# Main.net
KiCad netlist of a schematic drawn in Altium Designer
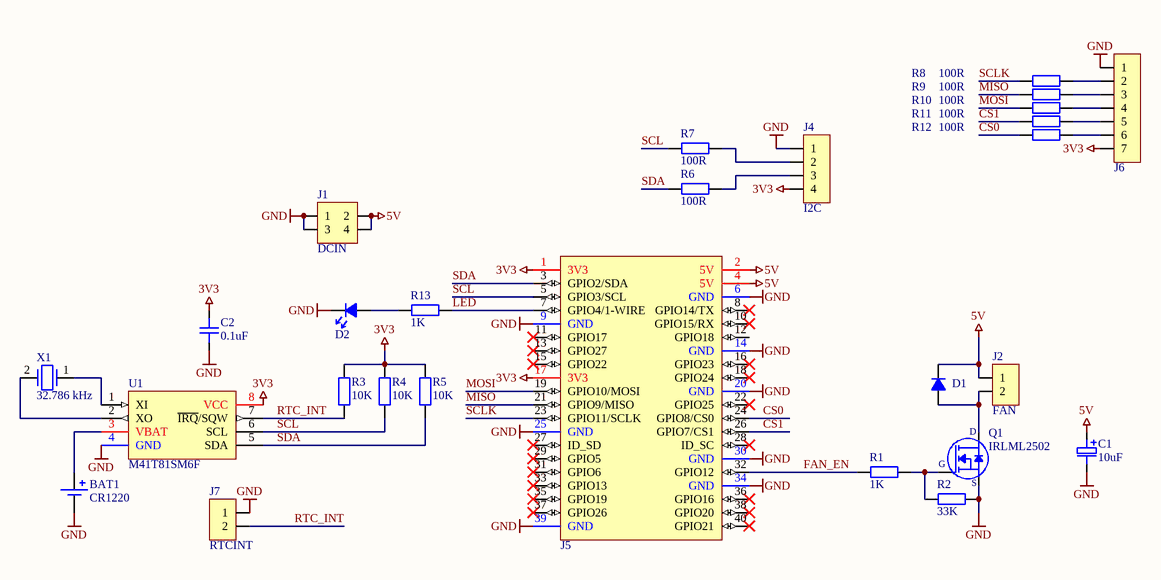
[diagram p0: Main.SchDoc]

(export (version "E")
  (design (tool "Eeschema 10.0.6"))
  (components
    (comp (ref "BAT1")
      (value "CR1220")
      (footprint "BC501SM")
      (description "Single Cell Battery")
      (libsource (lib "AG.Holder") (part "BC501SM"))
    )
    (comp (ref "C1")
      (value "10uF")
      (footprint "C_EL_B_4MM_RF_M")
      (description "Polarized Capacitor")
      (fields (field (name "TOLERANCE") "?") (field (name "MANUFACTURER") "Generic Brand"))
      (libsource (lib "AG.Generic") (part "C-P"))
    )
    (comp (ref "C2")
      (value "0.1uF")
      (footprint "0603C_RF_M")
      (description "Capacitor")
      (fields (field (name "TOLERANCE") "20%") (field (name "MANUFACTURER") "Generic Brand"))
      (libsource (lib "AG.Generic") (part "C"))
    )
    (comp (ref "D1")
      (value "D")
      (footprint "ONSEMI_DO214AC_RF_M")
      (description "Diode (Rectifier)")
      (fields (field (name "MANUFACTURER") "Generic Brand"))
      (libsource (lib "AG.Generic") (part "D"))
    )
    (comp (ref "D2")
      (value "Unspecified")
      (footprint "0805LED_RF_M")
      (description "LED")
      (fields (field (name "MANUFACTURER") "Generic Brand"))
      (libsource (lib "AG.Generic") (part "LED"))
    )
    (comp (ref "J1")
      (value "DCIN")
      (footprint "HEADER-2.54-4P-2R")
      (description "Rectangular Header Male Pins Double Row 4 Positions")
      (libsource (lib "AG.Connectors") (part "PINHDR-4P-2R"))
    )
    (comp (ref "J2")
      (value "FAN")
      (footprint "HEADER-2.54-2P1")
      (description "Pin Header Single Row 2 Positions")
      (libsource (lib "AG.Connectors") (part "PINHDR-2P1"))
    )
    (comp (ref "J4")
      (value "I2C")
      (footprint "AG.Connectors:HEADER-2.54-4P1")
      (description "Generic Pin Header 4x1")
      (libsource (lib "AG.Connectors") (part "PINHDR-4P1"))
    )
    (comp (ref "J5")
      (value "RPI4-40P")
      (footprint "HEADER-2.54-RCPT-40P-2R-BTL")
      (description "Raspberry Pi 4 Model B+ Compatible GPIO Header")
      (libsource (lib "AG.Connectors") (part "RPI4-40P"))
    )
    (comp (ref "J6")
      (value "PINHDR-7P1")
      (footprint "HEADER-2.54-7P1")
      (description "Pin Header Single Row 7 Positions")
      (libsource (lib "AG.Connectors") (part "PINHDR-7P1"))
    )
    (comp (ref "J7")
      (value "RTCINT")
      (footprint "HEADER-2.54-2P1")
      (description "Pin Header Single Row 2 Positions")
      (libsource (lib "") (part "PINHDR-2P1_1"))
    )
    (comp (ref "Q1")
      (value "IRLML2502")
      (footprint "IRLML_SOT-23")
      (description "MOSFET N-CH 20V 4.2A SOT23")
      (fields (field (name "MANUFACTURER") "Infineon") (field (name "MANUFACTURER PART NO") "IRLML2502TRPBF"))
      (libsource (lib "AG.Discrete") (part "IRLML2502"))
    )
    (comp (ref "R1")
      (value "1K")
      (footprint "0603R_RF_M")
      (description "Resistor")
      (fields (field (name "TOLERANCE") "?") (field (name "MANUFACTURER") "Generic Brand"))
      (libsource (lib "AG.Generic") (part "R"))
    )
    (comp (ref "R2")
      (value "33K")
      (footprint "0603R_RF_M")
      (description "Resistor")
      (fields (field (name "TOLERANCE") "?") (field (name "MANUFACTURER") "Generic Brand"))
      (libsource (lib "AG.Generic") (part "R"))
    )
    (comp (ref "R3")
      (value "10K")
      (footprint "0603R_RF_M")
      (description "Resistor")
      (fields (field (name "TOLERANCE") "?") (field (name "MANUFACTURER") "Generic Brand"))
      (libsource (lib "AG.Generic") (part "R"))
    )
    (comp (ref "R4")
      (value "10K")
      (footprint "0603R_RF_M")
      (description "Resistor")
      (fields (field (name "TOLERANCE") "?") (field (name "MANUFACTURER") "Generic Brand"))
      (libsource (lib "AG.Generic") (part "R"))
    )
    (comp (ref "R5")
      (value "10K")
      (footprint "0603R_RF_M")
      (description "Resistor")
      (fields (field (name "TOLERANCE") "?") (field (name "MANUFACTURER") "Generic Brand"))
      (libsource (lib "AG.Generic") (part "R"))
    )
    (comp (ref "R6")
      (value "100R")
      (footprint "0603R_RF_M")
      (description "Resistor")
      (fields (field (name "TOLERANCE") "?") (field (name "MANUFACTURER") "Generic Brand"))
      (libsource (lib "AG.Generic") (part "R"))
    )
    (comp (ref "R7")
      (value "100R")
      (footprint "0603R_RF_M")
      (description "Resistor")
      (fields (field (name "TOLERANCE") "?") (field (name "MANUFACTURER") "Generic Brand"))
      (libsource (lib "AG.Generic") (part "R"))
    )
    (comp (ref "R8")
      (value "100R")
      (footprint "0603R_RF_M")
      (description "Resistor")
      (fields (field (name "TOLERANCE") "?") (field (name "MANUFACTURER") "Generic Brand"))
      (libsource (lib "AG.Generic") (part "R"))
    )
    (comp (ref "R9")
      (value "100R")
      (footprint "0603R_RF_M")
      (description "Resistor")
      (fields (field (name "TOLERANCE") "?") (field (name "MANUFACTURER") "Generic Brand"))
      (libsource (lib "AG.Generic") (part "R"))
    )
    (comp (ref "R10")
      (value "100R")
      (footprint "0603R_RF_M")
      (description "Resistor")
      (fields (field (name "TOLERANCE") "?") (field (name "MANUFACTURER") "Generic Brand"))
      (libsource (lib "AG.Generic") (part "R"))
    )
    (comp (ref "R11")
      (value "100R")
      (footprint "0603R_RF_M")
      (description "Resistor")
      (fields (field (name "TOLERANCE") "?") (field (name "MANUFACTURER") "Generic Brand"))
      (libsource (lib "AG.Generic") (part "R"))
    )
    (comp (ref "R12")
      (value "100R")
      (footprint "0603R_RF_M")
      (description "Resistor")
      (fields (field (name "TOLERANCE") "?") (field (name "MANUFACTURER") "Generic Brand"))
      (libsource (lib "AG.Generic") (part "R"))
    )
    (comp (ref "R13")
      (value "1K")
      (footprint "0603R_RF_M")
      (description "Resistor")
      (fields (field (name "TOLERANCE") "?") (field (name "MANUFACTURER") "Generic Brand"))
      (libsource (lib "AG.Generic") (part "R"))
    )
    (comp (ref "U1")
      (value "M41T81SM6F")
      (footprint "ST_SOIC-8")
      (description "IC RTC CLK/CALENDAR I2C 8-SOIC")
      (fields
        (field (name "MANUFACTURER") "STMicroelectronics")
        (field (name "ALTERNATIVE SUPPLIER PART NO") "9000354105")
      )
      (libsource (lib "AG.IC") (part "M41T81SM6F"))
    )
    (comp (ref "X1")
      (value "32.786 kHz")
      (footprint "XTAL_3215")
      (description "Crystal Resonator (2 Leads)")
      (fields (field (name "MANUFACTURER") "Generic Brand") (field (name "TOLERANCE") "? ppm"))
      (libsource (lib "AG.Generic") (part "XT-2P"))
    )
  )
  (nets
    (net (code "1") (name "/CS0") (class "Default")
      (node (ref "J5") (pin "24") (pinfunction "GPIO8/CS0_24") (pintype "bidirectional"))
      (node (ref "R12") (pin "2") (pintype "passive"))
    )
    (net (code "2") (name "/CS1") (class "Default")
      (node (ref "J5") (pin "26") (pinfunction "GPIO7/CS1_26") (pintype "bidirectional"))
      (node (ref "R11") (pin "2") (pintype "passive"))
    )
    (net (code "3") (name "/FAN_EN") (class "Default")
      (node (ref "J5") (pin "32") (pinfunction "GPIO12_32") (pintype "bidirectional"))
      (node (ref "R1") (pin "1") (pintype "passive"))
    )
    (net (code "4") (name "/LED") (class "Default")
      (node (ref "J5") (pin "7") (pinfunction "GPIO4/1-WIRE_7") (pintype "bidirectional"))
      (node (ref "R13") (pin "1") (pintype "passive"))
    )
    (net (code "5") (name "/MISO") (class "Default")
      (node (ref "J5") (pin "21") (pinfunction "GPIO9/MISO_21") (pintype "bidirectional"))
      (node (ref "R9") (pin "2") (pintype "passive"))
    )
    (net (code "6") (name "/MOSI") (class "Default")
      (node (ref "J5") (pin "19") (pinfunction "GPIO10/MOSI_19") (pintype "bidirectional"))
      (node (ref "R10") (pin "2") (pintype "passive"))
    )
    (net (code "7") (name "/RTC_INT") (class "Default")
      (node (ref "J7") (pin "2") (pinfunction "2_2") (pintype "passive"))
      (node (ref "R3") (pin "1") (pintype "passive"))
      (node (ref "U1") (pin "7") (pinfunction "~{IRQ}/SQW_7") (pintype "output"))
    )
    (net (code "8") (name "/SCL") (class "Default")
      (node (ref "J5") (pin "5") (pinfunction "GPIO3/SCL_5") (pintype "bidirectional"))
      (node (ref "R4") (pin "1") (pintype "passive"))
      (node (ref "R7") (pin "2") (pintype "passive"))
      (node (ref "U1") (pin "6") (pinfunction "SCL_6") (pintype "open_collector"))
    )
    (net (code "9") (name "/SCLK") (class "Default")
      (node (ref "J5") (pin "23") (pinfunction "GPIO11/SCLK_23") (pintype "bidirectional"))
      (node (ref "R8") (pin "2") (pintype "passive"))
    )
    (net (code "10") (name "/SDA") (class "Default")
      (node (ref "J5") (pin "3") (pinfunction "GPIO2/SDA_3") (pintype "bidirectional"))
      (node (ref "R5") (pin "1") (pintype "passive"))
      (node (ref "R6") (pin "2") (pintype "passive"))
      (node (ref "U1") (pin "5") (pinfunction "SDA_5") (pintype "open_collector"))
    )
    (net (code "11") (name "3V3") (class "Default")
      (node (ref "C2") (pin "2") (pinfunction "2_2") (pintype "passive"))
      (node (ref "J4") (pin "4") (pinfunction "4_4") (pintype "passive"))
      (node (ref "J5") (pin "1") (pinfunction "3V3_1") (pintype "power_in"))
      (node (ref "J5") (pin "17") (pinfunction "3V3_17") (pintype "power_in"))
      (node (ref "J6") (pin "7") (pinfunction "7_7") (pintype "passive"))
      (node (ref "R3") (pin "2") (pintype "passive"))
      (node (ref "R4") (pin "2") (pintype "passive"))
      (node (ref "R5") (pin "2") (pintype "passive"))
      (node (ref "U1") (pin "8") (pinfunction "VCC_8") (pintype "power_in"))
    )
    (net (code "12") (name "5V") (class "Default")
      (node (ref "C1") (pin "P") (pinfunction "P_P") (pintype "power_in"))
      (node (ref "D1") (pin "C") (pinfunction "C_C") (pintype "passive"))
      (node (ref "J1") (pin "2") (pinfunction "2_2") (pintype "passive"))
      (node (ref "J1") (pin "4") (pinfunction "4_4") (pintype "passive"))
      (node (ref "J2") (pin "1") (pinfunction "1_1") (pintype "passive"))
      (node (ref "J5") (pin "2") (pinfunction "5V_2") (pintype "power_in"))
      (node (ref "J5") (pin "4") (pinfunction "5V_4") (pintype "power_in"))
    )
    (net (code "13") (name "GND") (class "Default")
      (node (ref "BAT1") (pin "N") (pinfunction "N_N") (pintype "power_in"))
      (node (ref "C1") (pin "N") (pinfunction "N_N") (pintype "power_in"))
      (node (ref "C2") (pin "1") (pinfunction "1_1") (pintype "passive"))
      (node (ref "D2") (pin "C") (pinfunction "C_C") (pintype "passive"))
      (node (ref "J1") (pin "1") (pinfunction "1_1") (pintype "passive"))
      (node (ref "J1") (pin "3") (pinfunction "3_3") (pintype "passive"))
      (node (ref "J4") (pin "1") (pinfunction "1_1") (pintype "passive"))
      (node (ref "J5") (pin "14") (pinfunction "GND_14") (pintype "power_in"))
      (node (ref "J5") (pin "20") (pinfunction "GND_20") (pintype "power_in"))
      (node (ref "J5") (pin "25") (pinfunction "GND_25") (pintype "power_in"))
      (node (ref "J5") (pin "30") (pinfunction "GND_30") (pintype "power_in"))
      (node (ref "J5") (pin "34") (pinfunction "GND_34") (pintype "power_in"))
      (node (ref "J5") (pin "39") (pinfunction "GND_39") (pintype "power_in"))
      (node (ref "J5") (pin "6") (pinfunction "GND_6") (pintype "power_in"))
      (node (ref "J5") (pin "9") (pinfunction "GND_9") (pintype "power_in"))
      (node (ref "J6") (pin "1") (pinfunction "1_1") (pintype "passive"))
      (node (ref "J7") (pin "1") (pinfunction "1_1") (pintype "passive"))
      (node (ref "Q1") (pin "2") (pinfunction "S_2") (pintype "passive"))
      (node (ref "R2") (pin "2") (pintype "passive"))
      (node (ref "U1") (pin "4") (pinfunction "GND_4") (pintype "power_in"))
    )
    (net (code "14") (name "Net-(D2-PadA)") (class "Default")
      (node (ref "D2") (pin "A") (pinfunction "A_A") (pintype "passive"))
      (node (ref "R13") (pin "2") (pintype "passive"))
    )
    (net (code "15") (name "Net-(J4-Pad2)") (class "Default")
      (node (ref "J4") (pin "2") (pinfunction "2_2") (pintype "passive"))
      (node (ref "R7") (pin "1") (pintype "passive"))
    )
    (net (code "16") (name "Net-(J4-Pad3)") (class "Default")
      (node (ref "J4") (pin "3") (pinfunction "3_3") (pintype "passive"))
      (node (ref "R6") (pin "1") (pintype "passive"))
    )
    (net (code "17") (name "Net-(J6-Pad2)") (class "Default")
      (node (ref "J6") (pin "2") (pinfunction "2_2") (pintype "passive"))
      (node (ref "R8") (pin "1") (pintype "passive"))
    )
    (net (code "18") (name "Net-(J6-Pad3)") (class "Default")
      (node (ref "J6") (pin "3") (pinfunction "3_3") (pintype "passive"))
      (node (ref "R9") (pin "1") (pintype "passive"))
    )
    (net (code "19") (name "Net-(J6-Pad4)") (class "Default")
      (node (ref "J6") (pin "4") (pinfunction "4_4") (pintype "passive"))
      (node (ref "R10") (pin "1") (pintype "passive"))
    )
    (net (code "20") (name "Net-(J6-Pad5)") (class "Default")
      (node (ref "J6") (pin "5") (pinfunction "5_5") (pintype "passive"))
      (node (ref "R11") (pin "1") (pintype "passive"))
    )
    (net (code "21") (name "Net-(J6-Pad6)") (class "Default")
      (node (ref "J6") (pin "6") (pinfunction "6_6") (pintype "passive"))
      (node (ref "R12") (pin "1") (pintype "passive"))
    )
    (net (code "22") (name "Net-(Q1-D)") (class "Default")
      (node (ref "D1") (pin "A") (pinfunction "A_A") (pintype "passive"))
      (node (ref "J2") (pin "2") (pinfunction "2_2") (pintype "passive"))
      (node (ref "Q1") (pin "3") (pinfunction "D_3") (pintype "passive"))
    )
    (net (code "23") (name "Net-(Q1-G)") (class "Default")
      (node (ref "Q1") (pin "1") (pinfunction "G_1") (pintype "passive"))
      (node (ref "R1") (pin "2") (pintype "passive"))
      (node (ref "R2") (pin "1") (pintype "passive"))
    )
    (net (code "24") (name "Net-(U1-VBAT)") (class "Default")
      (node (ref "BAT1") (pin "P") (pinfunction "P_P") (pintype "power_in"))
      (node (ref "U1") (pin "3") (pinfunction "VBAT_3") (pintype "power_in"))
    )
    (net (code "25") (name "Net-(U1-XI)") (class "Default")
      (node (ref "U1") (pin "1") (pinfunction "XI_1") (pintype "input"))
      (node (ref "X1") (pin "1") (pinfunction "1_1") (pintype "passive"))
    )
    (net (code "26") (name "Net-(U1-XO)") (class "Default")
      (node (ref "U1") (pin "2") (pinfunction "XO_2") (pintype "output"))
      (node (ref "X1") (pin "2") (pinfunction "2_2") (pintype "passive"))
    )
    (net (code "27") (name "unconnected-(J5-GPIO5-Pad29)") (class "Default")
      (node (ref "J5") (pin "29") (pinfunction "GPIO5_29") (pintype "bidirectional+no_connect"))
    )
    (net (code "28") (name "unconnected-(J5-GPIO6-Pad31)") (class "Default")
      (node (ref "J5") (pin "31") (pinfunction "GPIO6_31") (pintype "bidirectional+no_connect"))
    )
    (net (code "29") (name "unconnected-(J5-GPIO13-Pad33)") (class "Default")
      (node (ref "J5") (pin "33") (pinfunction "GPIO13_33") (pintype "bidirectional+no_connect"))
    )
    (net (code "30") (name "unconnected-(J5-GPIO14{slash}TX-Pad8)") (class "Default")
      (node (ref "J5") (pin "8") (pinfunction "GPIO14/TX_8") (pintype "bidirectional+no_connect"))
    )
    (net (code "31") (name "unconnected-(J5-GPIO15{slash}RX-Pad10)") (class "Default")
      (node (ref "J5") (pin "10") (pinfunction "GPIO15/RX_10") (pintype "bidirectional+no_connect"))
    )
    (net (code "32") (name "unconnected-(J5-GPIO16-Pad36)") (class "Default")
      (node (ref "J5") (pin "36") (pinfunction "GPIO16_36") (pintype "bidirectional+no_connect"))
    )
    (net (code "33") (name "unconnected-(J5-GPIO17-Pad11)") (class "Default")
      (node (ref "J5") (pin "11") (pinfunction "GPIO17_11") (pintype "bidirectional+no_connect"))
    )
    (net (code "34") (name "unconnected-(J5-GPIO18-Pad12)") (class "Default")
      (node (ref "J5") (pin "12") (pinfunction "GPIO18_12") (pintype "bidirectional"))
    )
    (net (code "35") (name "unconnected-(J5-GPIO19-Pad35)") (class "Default")
      (node (ref "J5") (pin "35") (pinfunction "GPIO19_35") (pintype "bidirectional+no_connect"))
    )
    (net (code "36") (name "unconnected-(J5-GPIO20-Pad38)") (class "Default")
      (node (ref "J5") (pin "38") (pinfunction "GPIO20_38") (pintype "bidirectional+no_connect"))
    )
    (net (code "37") (name "unconnected-(J5-GPIO21-Pad40)") (class "Default")
      (node (ref "J5") (pin "40") (pinfunction "GPIO21_40") (pintype "bidirectional+no_connect"))
    )
    (net (code "38") (name "unconnected-(J5-GPIO22-Pad15)") (class "Default")
      (node (ref "J5") (pin "15") (pinfunction "GPIO22_15") (pintype "bidirectional+no_connect"))
    )
    (net (code "39") (name "unconnected-(J5-GPIO23-Pad16)") (class "Default")
      (node (ref "J5") (pin "16") (pinfunction "GPIO23_16") (pintype "bidirectional+no_connect"))
    )
    (net (code "40") (name "unconnected-(J5-GPIO24-Pad18)") (class "Default")
      (node (ref "J5") (pin "18") (pinfunction "GPIO24_18") (pintype "bidirectional+no_connect"))
    )
    (net (code "41") (name "unconnected-(J5-GPIO25-Pad22)") (class "Default")
      (node (ref "J5") (pin "22") (pinfunction "GPIO25_22") (pintype "bidirectional+no_connect"))
    )
    (net (code "42") (name "unconnected-(J5-GPIO26-Pad37)") (class "Default")
      (node (ref "J5") (pin "37") (pinfunction "GPIO26_37") (pintype "bidirectional+no_connect"))
    )
    (net (code "43") (name "unconnected-(J5-GPIO27-Pad13)") (class "Default")
      (node (ref "J5") (pin "13") (pinfunction "GPIO27_13") (pintype "bidirectional+no_connect"))
    )
    (net (code "44") (name "unconnected-(J5-ID_SC-Pad28)") (class "Default")
      (node (ref "J5") (pin "28") (pinfunction "ID_SC_28") (pintype "bidirectional+no_connect"))
    )
    (net (code "45") (name "unconnected-(J5-ID_SD-Pad27)") (class "Default")
      (node (ref "J5") (pin "27") (pinfunction "ID_SD_27") (pintype "bidirectional+no_connect"))
    )
  )
)
